# gray_steer_detor.net
KiCad netlist of a schematic drawn in EAGLE
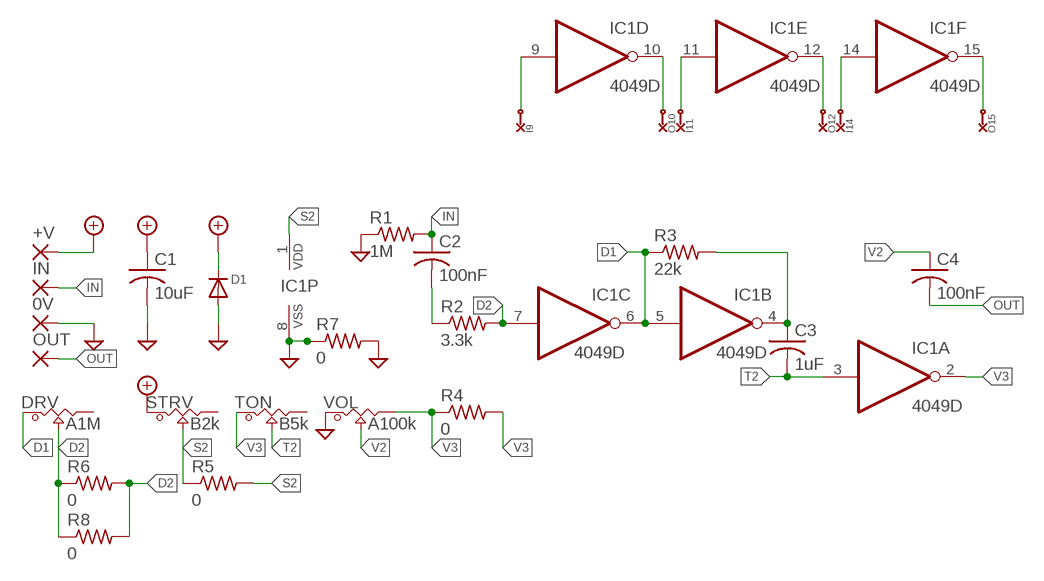
[diagram p0: schematic, sheet 1]

(export (version "E")
  (design (tool "Eeschema 10.0.6"))
  (components
    (comp (ref "+V")
      (value "SMD2")
      (footprint "eagle-import:SMD1,27-2,54")
      (libsource (lib "eagle-import") (part "SMD2"))
    )
    (comp (ref "0V")
      (value "SMD2")
      (footprint "eagle-import:SMD1,27-2,54")
      (libsource (lib "eagle-import") (part "SMD2"))
    )
    (comp (ref "C1")
      (value "10uF")
      (footprint "eagle-import:C1206")
      (libsource (lib "eagle-import") (part "C-USC1206"))
    )
    (comp (ref "C2")
      (value "100nF")
      (footprint "eagle-import:C0603")
      (libsource (lib "eagle-import") (part "C-USC0603"))
    )
    (comp (ref "C3")
      (value "1uF")
      (footprint "eagle-import:C0603")
      (libsource (lib "eagle-import") (part "C-USC0603"))
    )
    (comp (ref "C4")
      (value "100nF")
      (footprint "eagle-import:C0603")
      (libsource (lib "eagle-import") (part "C-USC0603"))
    )
    (comp (ref "D1")
      (value "DIODESOD-123")
      (footprint "eagle-import:SOD-123")
      (libsource (lib "eagle-import") (part "DIODESOD-123"))
    )
    (comp (ref "DRV")
      (value "A1M")
      (footprint "eagle-import:POT_9MM_SMD")
      (libsource (lib "eagle-import") (part "POT_9MM_SMD"))
    )
    (comp (ref "I9")
      (value "COM_SMD")
      (footprint "eagle-import:1PAD")
      (libsource (lib "eagle-import") (part "COM_SMD"))
    )
    (comp (ref "I11")
      (value "COM_SMD")
      (footprint "eagle-import:1PAD")
      (libsource (lib "eagle-import") (part "COM_SMD"))
    )
    (comp (ref "I14")
      (value "COM_SMD")
      (footprint "eagle-import:1PAD")
      (libsource (lib "eagle-import") (part "COM_SMD"))
    )
    (comp (ref "IC1")
      (value "4049D")
      (footprint "eagle-import:SO16")
      (libsource (lib "eagle-import") (part "4049D"))
    )
    (comp (ref "IN")
      (value "SMD2")
      (footprint "eagle-import:SMD1,27-2,54")
      (libsource (lib "eagle-import") (part "SMD2"))
    )
    (comp (ref "O10")
      (value "COM_SMD")
      (footprint "eagle-import:1PAD")
      (libsource (lib "eagle-import") (part "COM_SMD"))
    )
    (comp (ref "O12")
      (value "COM_SMD")
      (footprint "eagle-import:1PAD")
      (libsource (lib "eagle-import") (part "COM_SMD"))
    )
    (comp (ref "O15")
      (value "COM_SMD")
      (footprint "eagle-import:1PAD")
      (libsource (lib "eagle-import") (part "COM_SMD"))
    )
    (comp (ref "OUT")
      (value "SMD2")
      (footprint "eagle-import:SMD1,27-2,54")
      (libsource (lib "eagle-import") (part "SMD2"))
    )
    (comp (ref "R1")
      (value "1M")
      (footprint "eagle-import:R0603")
      (libsource (lib "eagle-import") (part "R-US_R0603"))
    )
    (comp (ref "R2")
      (value "3.3k")
      (footprint "eagle-import:R0603")
      (libsource (lib "eagle-import") (part "R-US_R0603"))
    )
    (comp (ref "R3")
      (value "22k")
      (footprint "eagle-import:R0603")
      (libsource (lib "eagle-import") (part "R-US_R0603"))
    )
    (comp (ref "R4")
      (value "0")
      (footprint "eagle-import:R0402")
      (libsource (lib "eagle-import") (part "R-US_R0402"))
    )
    (comp (ref "R5")
      (value "0")
      (footprint "eagle-import:R0402")
      (libsource (lib "eagle-import") (part "R-US_R0402"))
    )
    (comp (ref "R6")
      (value "0")
      (footprint "eagle-import:R0402")
      (libsource (lib "eagle-import") (part "R-US_R0402"))
    )
    (comp (ref "R7")
      (value "0")
      (footprint "eagle-import:R0402")
      (libsource (lib "eagle-import") (part "R-US_R0402"))
    )
    (comp (ref "R8")
      (value "0")
      (footprint "eagle-import:R0402")
      (libsource (lib "eagle-import") (part "R-US_R0402"))
    )
    (comp (ref "STRV")
      (value "B2k")
      (footprint "eagle-import:POT_9MM_SMD")
      (libsource (lib "eagle-import") (part "POT_9MM_SMD"))
    )
    (comp (ref "TON")
      (value "B5k")
      (footprint "eagle-import:POT_9MM_SMD")
      (libsource (lib "eagle-import") (part "POT_9MM_SMD"))
    )
    (comp (ref "VOL")
      (value "A100k")
      (footprint "eagle-import:POT_9MM_SMD")
      (libsource (lib "eagle-import") (part "POT_9MM_SMD"))
    )
  )
  (nets
    (net (code "1") (name "+9V") (class "Default")
      (node (ref "+V") (pin "1") (pinfunction "P_1") (pintype "passive"))
      (node (ref "C1") (pin "1") (pinfunction "1_1") (pintype "passive"))
      (node (ref "D1") (pin "C") (pinfunction "C_C") (pintype "passive"))
      (node (ref "STRV") (pin "1") (pinfunction "1_1") (pintype "bidirectional"))
    )
    (net (code "2") (name "D1") (class "Default")
      (node (ref "DRV") (pin "1") (pinfunction "1_1") (pintype "bidirectional"))
      (node (ref "IC1") (pin "5") (pinfunction "I_5") (pintype "input"))
      (node (ref "IC1") (pin "6") (pinfunction "O_6") (pintype "output"))
      (node (ref "R3") (pin "1") (pinfunction "1_1") (pintype "passive"))
    )
    (net (code "3") (name "D2") (class "Default")
      (node (ref "DRV") (pin "2") (pinfunction "2_2") (pintype "bidirectional"))
      (node (ref "IC1") (pin "7") (pinfunction "I_7") (pintype "input"))
      (node (ref "R2") (pin "2") (pinfunction "2_2") (pintype "passive"))
      (node (ref "R6") (pin "1") (pinfunction "1_1") (pintype "passive"))
      (node (ref "R6") (pin "2") (pinfunction "2_2") (pintype "passive"))
      (node (ref "R8") (pin "1") (pinfunction "1_1") (pintype "passive"))
      (node (ref "R8") (pin "2") (pinfunction "2_2") (pintype "passive"))
    )
    (net (code "4") (name "GND") (class "Default")
      (node (ref "0V") (pin "1") (pinfunction "P_1") (pintype "passive"))
      (node (ref "C1") (pin "2") (pinfunction "2_2") (pintype "passive"))
      (node (ref "D1") (pin "A") (pinfunction "A_A") (pintype "passive"))
      (node (ref "IC1") (pin "8") (pinfunction "VSS_8") (pintype "power_in"))
      (node (ref "R1") (pin "1") (pinfunction "1_1") (pintype "passive"))
      (node (ref "R7") (pin "1") (pinfunction "1_1") (pintype "passive"))
      (node (ref "R7") (pin "2") (pinfunction "2_2") (pintype "passive"))
      (node (ref "VOL") (pin "1") (pinfunction "1_1") (pintype "bidirectional"))
    )
    (net (code "5") (name "IN") (class "Default")
      (node (ref "C2") (pin "1") (pinfunction "1_1") (pintype "passive"))
      (node (ref "IN") (pin "1") (pinfunction "P_1") (pintype "passive"))
      (node (ref "R1") (pin "2") (pinfunction "2_2") (pintype "passive"))
    )
    (net (code "6") (name "Net-(C2-Pad2)") (class "Default")
      (node (ref "C2") (pin "2") (pinfunction "2_2") (pintype "passive"))
      (node (ref "R2") (pin "1") (pinfunction "1_1") (pintype "passive"))
    )
    (net (code "7") (name "Net-(IC1B-O)") (class "Default")
      (node (ref "C3") (pin "1") (pinfunction "1_1") (pintype "passive"))
      (node (ref "IC1") (pin "4") (pinfunction "O_4") (pintype "output"))
      (node (ref "R3") (pin "2") (pinfunction "2_2") (pintype "passive"))
    )
    (net (code "8") (name "Net-(IC1D-I)") (class "Default")
      (node (ref "I9") (pin "1") (pinfunction "1_1") (pintype "bidirectional"))
      (node (ref "IC1") (pin "9") (pinfunction "I_9") (pintype "input"))
    )
    (net (code "9") (name "Net-(IC1D-O)") (class "Default")
      (node (ref "IC1") (pin "10") (pinfunction "O_10") (pintype "output"))
      (node (ref "O10") (pin "1") (pinfunction "1_1") (pintype "bidirectional"))
    )
    (net (code "10") (name "Net-(IC1E-I)") (class "Default")
      (node (ref "I11") (pin "1") (pinfunction "1_1") (pintype "bidirectional"))
      (node (ref "IC1") (pin "11") (pinfunction "I_11") (pintype "input"))
    )
    (net (code "11") (name "Net-(IC1E-O)") (class "Default")
      (node (ref "IC1") (pin "12") (pinfunction "O_12") (pintype "output"))
      (node (ref "O12") (pin "1") (pinfunction "1_1") (pintype "bidirectional"))
    )
    (net (code "12") (name "Net-(IC1F-I)") (class "Default")
      (node (ref "I14") (pin "1") (pinfunction "1_1") (pintype "bidirectional"))
      (node (ref "IC1") (pin "14") (pinfunction "I_14") (pintype "input"))
    )
    (net (code "13") (name "Net-(IC1F-O)") (class "Default")
      (node (ref "IC1") (pin "15") (pinfunction "O_15") (pintype "output"))
      (node (ref "O15") (pin "1") (pinfunction "1_1") (pintype "bidirectional"))
    )
    (net (code "14") (name "OUT") (class "Default")
      (node (ref "C4") (pin "2") (pinfunction "2_2") (pintype "passive"))
      (node (ref "OUT") (pin "1") (pinfunction "P_1") (pintype "passive"))
    )
    (net (code "15") (name "S2") (class "Default")
      (node (ref "IC1") (pin "1") (pinfunction "VDD_1") (pintype "power_in"))
      (node (ref "R5") (pin "1") (pinfunction "1_1") (pintype "passive"))
      (node (ref "R5") (pin "2") (pinfunction "2_2") (pintype "passive"))
      (node (ref "STRV") (pin "2") (pinfunction "2_2") (pintype "bidirectional"))
    )
    (net (code "16") (name "T2") (class "Default")
      (node (ref "C3") (pin "2") (pinfunction "2_2") (pintype "passive"))
      (node (ref "IC1") (pin "3") (pinfunction "I_3") (pintype "input"))
      (node (ref "TON") (pin "2") (pinfunction "2_2") (pintype "bidirectional"))
    )
    (net (code "17") (name "V2") (class "Default")
      (node (ref "C4") (pin "1") (pinfunction "1_1") (pintype "passive"))
      (node (ref "VOL") (pin "2") (pinfunction "2_2") (pintype "bidirectional"))
    )
    (net (code "18") (name "V3") (class "Default")
      (node (ref "IC1") (pin "2") (pinfunction "O_2") (pintype "output"))
      (node (ref "R4") (pin "1") (pinfunction "1_1") (pintype "passive"))
      (node (ref "R4") (pin "2") (pinfunction "2_2") (pintype "passive"))
      (node (ref "TON") (pin "1") (pinfunction "1_1") (pintype "bidirectional"))
      (node (ref "VOL") (pin "3") (pinfunction "3_3") (pintype "bidirectional"))
    )
    (net (code "19") (name "unconnected-(DRV-Pad3)") (class "Default")
      (node (ref "DRV") (pin "3") (pinfunction "3_3") (pintype "bidirectional"))
    )
    (net (code "20") (name "unconnected-(STRV-Pad3)") (class "Default")
      (node (ref "STRV") (pin "3") (pinfunction "3_3") (pintype "bidirectional"))
    )
    (net (code "21") (name "unconnected-(TON-Pad3)") (class "Default")
      (node (ref "TON") (pin "3") (pinfunction "3_3") (pintype "bidirectional"))
    )
  )
)
